# JDDZ.net
KiCad netlist of a schematic drawn in Altium Designer
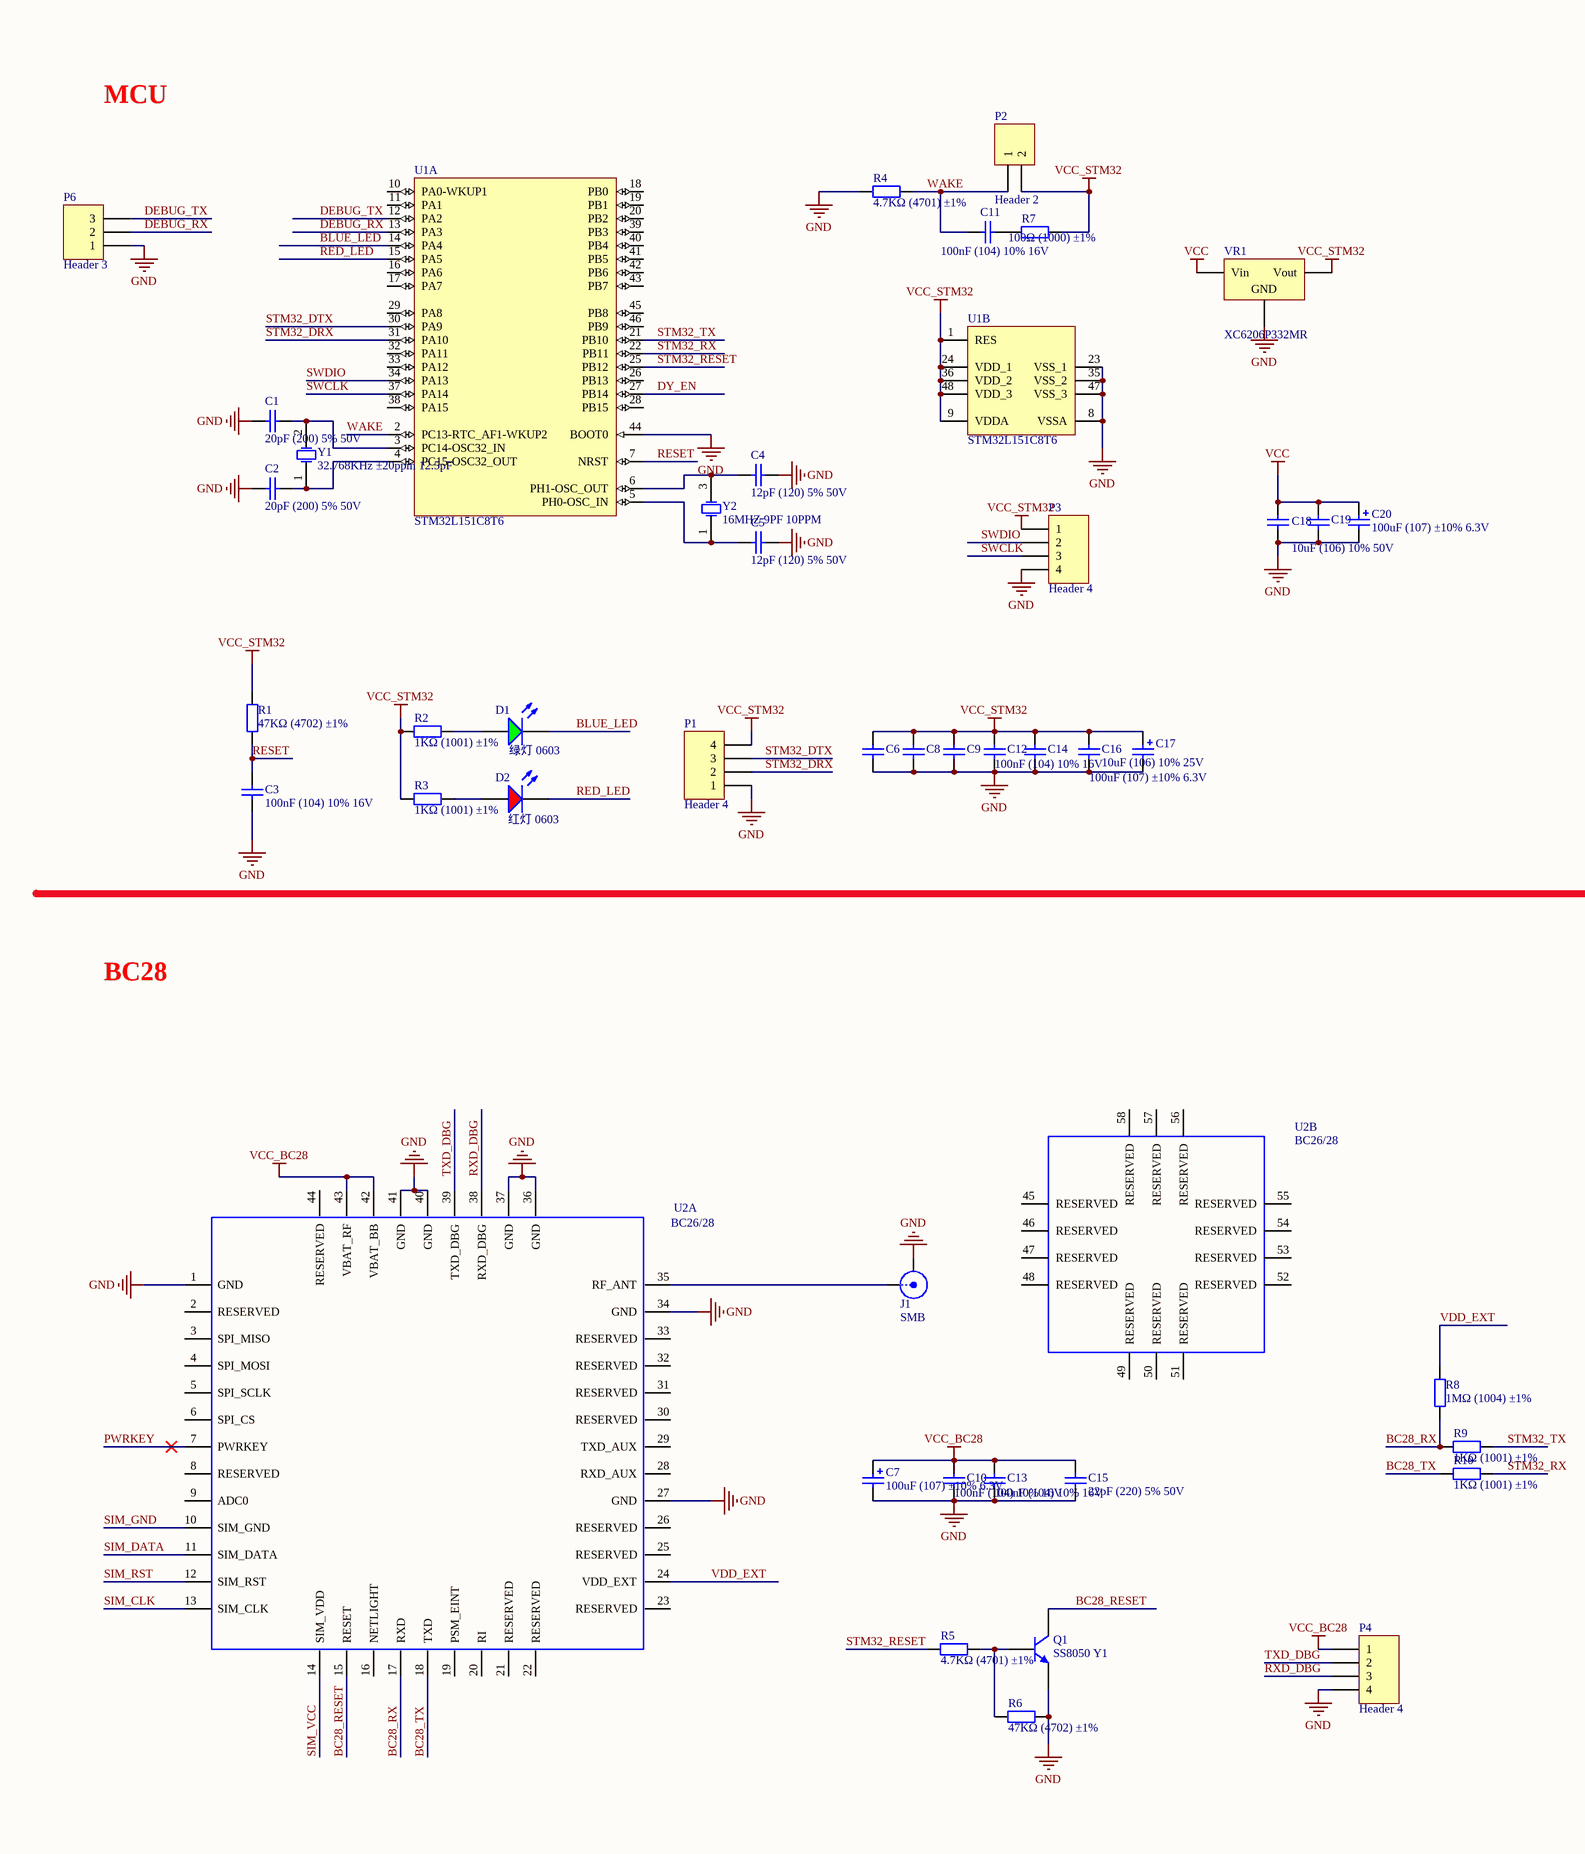
[diagram p0: JDDZ.SchDoc, left]
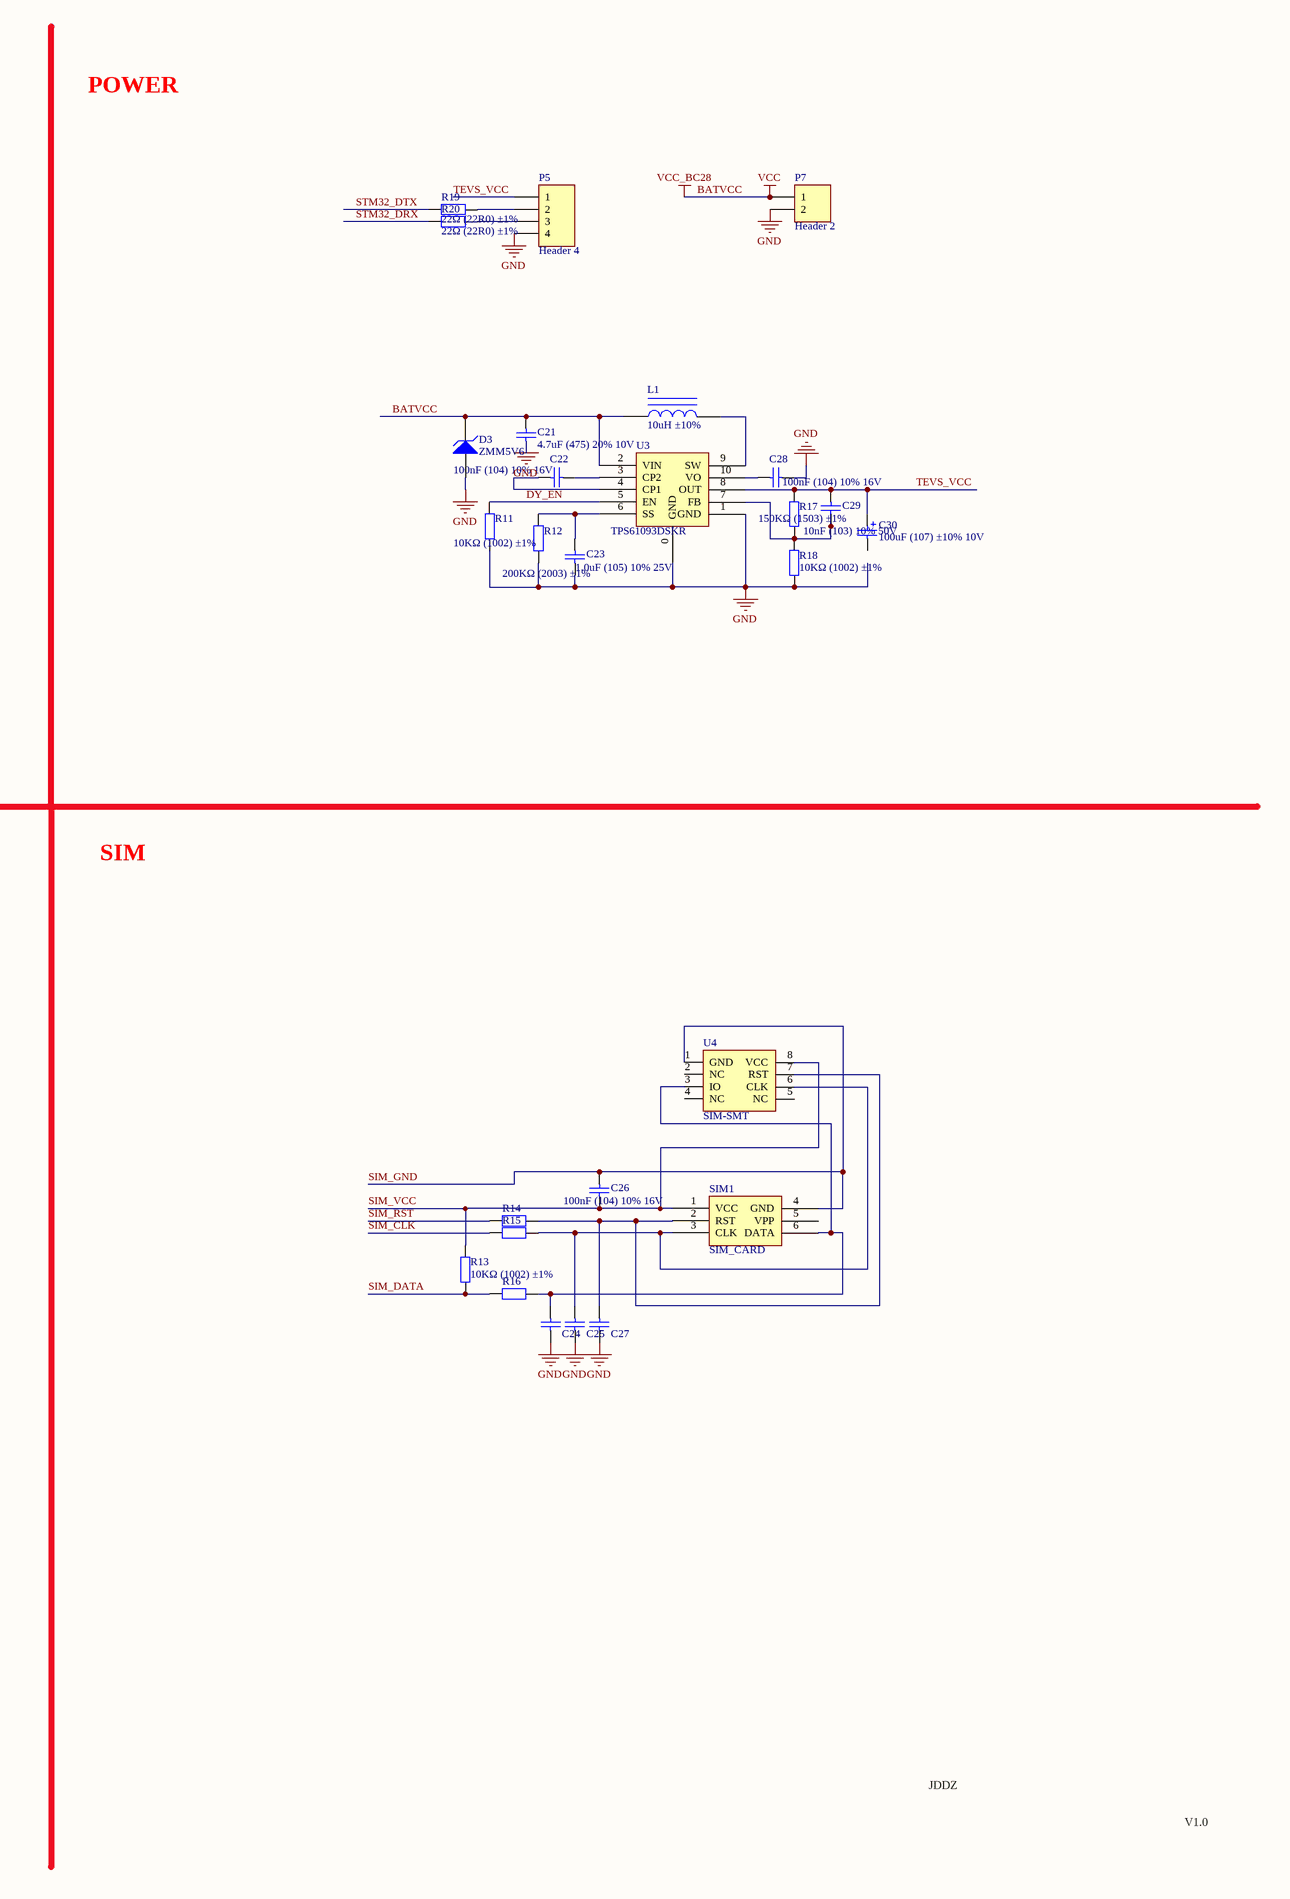
[diagram p1: JDDZ.SchDoc, right]

(export (version "E")
  (design (tool "Eeschema 10.0.6"))
  (components
    (comp (ref "C1")
      (value "20pF (200) 5% 50V")
      (footprint "0402_C")
      (description "贴片电容")
      (libsource (lib "Cap") (part "0402 20pF (200) 5% 50V"))
    )
    (comp (ref "C2")
      (value "20pF (200) 5% 50V")
      (footprint "0402_C")
      (description "贴片电容")
      (libsource (lib "Cap") (part "0402 20pF (200) 5% 50V"))
    )
    (comp (ref "C3")
      (value "100nF (104) 10% 16V")
      (footprint "0402_C")
      (description "贴片电容")
      (libsource (lib "Cap") (part "0402 100nF (104) 10% 16V"))
    )
    (comp (ref "C4")
      (value "12pF (120) 5% 50V")
      (footprint "0402_C")
      (description "贴片电容")
      (libsource (lib "Cap") (part "0402 12pF (120) 5% 50V"))
    )
    (comp (ref "C5")
      (value "12pF (120) 5% 50V")
      (footprint "0402_C")
      (description "贴片电容")
      (libsource (lib "Cap") (part "0402 12pF (120) 5% 50V"))
    )
    (comp (ref "C6")
      (value "100nF (104) 10% 16V")
      (footprint "0402_C")
      (description "贴片电容")
      (libsource (lib "Cap") (part "0402 100nF (104) 10% 16V"))
    )
    (comp (ref "C7")
      (value "100uF (107) ±10% 6.3V")
      (footprint "CASE-B_3528")
      (description "钽电容")
      (libsource (lib "Cap") (part "3528 100uF (107) 10% 6.3V"))
    )
    (comp (ref "C8")
      (value "100nF (104) 10% 16V")
      (footprint "0402_C")
      (description "贴片电容")
      (libsource (lib "Cap") (part "0402 100nF (104) 10% 16V"))
    )
    (comp (ref "C9")
      (value "100nF (104) 10% 16V")
      (footprint "0402_C")
      (description "贴片电容")
      (libsource (lib "Cap") (part "0402 100nF (104) 10% 16V"))
    )
    (comp (ref "C10")
      (value "100nF (104) 10% 16V")
      (footprint "0402_C")
      (description "贴片电容")
      (libsource (lib "Cap") (part "0402 100nF (104) 10% 16V"))
    )
    (comp (ref "C11")
      (value "100nF (104) 10% 16V")
      (footprint "0402_C")
      (description "贴片电容")
      (libsource (lib "Cap") (part "0402 100nF (104) 10% 16V"))
    )
    (comp (ref "C12")
      (value "100nF (104) 10% 16V")
      (footprint "0402_C")
      (description "贴片电容")
      (libsource (lib "Cap") (part "0402 100nF (104) 10% 16V"))
    )
    (comp (ref "C13")
      (value "100nF (104) 10% 16V")
      (footprint "0402_C")
      (description "贴片电容")
      (libsource (lib "Cap") (part "0402 100nF (104) 10% 16V"))
    )
    (comp (ref "C14")
      (value "100nF (104) 10% 16V")
      (footprint "0402_C")
      (description "贴片电容")
      (libsource (lib "Cap") (part "0402 100nF (104) 10% 16V"))
    )
    (comp (ref "C15")
      (value "22pF (220) 5% 50V")
      (footprint "0402_C")
      (description "贴片电容")
      (libsource (lib "Cap") (part "0402 22pF (220) 5% 50V"))
    )
    (comp (ref "C16")
      (value "10uF (106) 10% 25V")
      (footprint "0805_C")
      (description "贴片电容")
      (libsource (lib "Cap") (part "0805 10uF (106) 10% 25V"))
    )
    (comp (ref "C17")
      (value "100uF (107) ±10% 6.3V")
      (footprint "CASE-B_3528")
      (description "钽电容")
      (libsource (lib "Cap") (part "3528 100uF (107) 10% 6.3V"))
    )
    (comp (ref "C18")
      (value "10uF (106) 10% 10V")
      (footprint "0603_C")
      (description "贴片电容")
      (libsource (lib "Miscellaneous Devices LC") (part "0603 10uF (106) 10% 10V"))
    )
    (comp (ref "C19")
      (value "10uF (106) 10% 50V")
      (footprint "1206_C")
      (description "贴片电容")
      (libsource (lib "Miscellaneous Devices LC") (part "1206 10uF (106) 10% 50V"))
    )
    (comp (ref "C20")
      (value "100uF (107) ±10% 6.3V")
      (footprint "CASE-B_3528")
      (description "钽电容")
      (libsource (lib "Cap") (part "3528 100uF (107) 10% 6.3V"))
    )
    (comp (ref "C21")
      (value "4.7uF (475) 20% 10V")
      (footprint "0402_C")
      (description "贴片电容")
      (libsource (lib "Miscellaneous Devices LC") (part "0402 4.7uF (475) 20% 10V"))
    )
    (comp (ref "C22")
      (value "100nF (104) 10% 16V")
      (footprint "0402_C")
      (description "贴片电容")
      (libsource (lib "Miscellaneous Devices LC") (part "0402 100nF (104) 10% 16V"))
    )
    (comp (ref "C23")
      (value "1.0uF (105) 10% 25V")
      (footprint "0402_C")
      (description "贴片电容")
      (libsource (lib "Miscellaneous Devices LC") (part "0402 1.0uF (105) 10% 25V"))
    )
    (comp (ref "C24")
      (value "33pF (330) 5% 50V")
      (footprint "0402_C")
      (description "贴片电容")
      (libsource (lib "Cap") (part "0402 33pF (330) 5% 50V"))
    )
    (comp (ref "C25")
      (value "33pF (330) 5% 50V")
      (footprint "0402_C")
      (description "贴片电容")
      (libsource (lib "Cap") (part "0402 33pF (330) 5% 50V"))
    )
    (comp (ref "C26")
      (value "100nF (104) 10% 16V")
      (footprint "0402_C")
      (description "贴片电容")
      (libsource (lib "Cap") (part "0402 100nF (104) 10% 16V"))
    )
    (comp (ref "C27")
      (value "33pF (330) 5% 50V")
      (footprint "0402_C")
      (description "贴片电容")
      (libsource (lib "Cap") (part "0402 33pF (330) 5% 50V"))
    )
    (comp (ref "C28")
      (value "100nF (104) 10% 16V")
      (footprint "0402_C")
      (description "贴片电容")
      (libsource (lib "Miscellaneous Devices LC") (part "0402 100nF (104) 10% 16V"))
    )
    (comp (ref "C29")
      (value "10nF (103) 10% 50V")
      (footprint "0402_C")
      (description "贴片电容")
      (libsource (lib "Miscellaneous Devices LC") (part "0402 10nF (103) 10% 50V"))
    )
    (comp (ref "C30")
      (value "100uF (107) ±10% 10V")
      (footprint "CASE-B_3528")
      (description "钽电容")
      (libsource (lib "Miscellaneous Devices LC") (part "3528 100uF (107) 10% 6.3V"))
    )
    (comp (ref "D1")
      (value "绿灯 0603")
      (footprint "0603_LED_S1")
      (description "发光二极管")
      (libsource (lib "LED") (part "0603 绿灯"))
    )
    (comp (ref "D2")
      (value "红灯 0603")
      (footprint "0603_LED_S1")
      (description "发光二极管")
      (libsource (lib "LED") (part "0603 红灯"))
    )
    (comp (ref "D3")
      (value "ZMM5V6")
      (footprint "LL-34")
      (description "稳压二极管")
      (libsource (lib "Zener") (part "LL-34 ZMM5V6"))
    )
    (comp (ref "J1")
      (value "SMB")
      (footprint "IPX_SMT")
      (description "SMB Straight Connector")
      (fields (field (name "PUBLISHER") "Altium Limited"))
      (libsource (lib "BC28开发板SCH封装") (part "SMB"))
    )
    (comp (ref "L1")
      (value "10uH ±10%")
      (footprint "0603_L")
      (description "贴片电感")
      (libsource (lib "Miscellaneous Devices LC") (part "0603 10uH 10%"))
    )
    (comp (ref "P1")
      (value "Header 4")
      (footprint "HDR1X4")
      (description "Header, 4-Pin")
      (fields (field (name "PUBLISHER") "Altium Limited"))
      (libsource (lib "") (part "Header 4_1"))
    )
    (comp (ref "P2")
      (value "Header 2")
      (footprint "HDR1X2")
      (description "Header, 2-Pin")
      (fields (field (name "PUBLISHER") "Altium Limited"))
      (libsource (lib "Miscellaneous Connectors") (part "Header 2"))
    )
    (comp (ref "P3")
      (value "Header 4")
      (footprint "HDR1X4")
      (description "Header, 4-Pin")
      (fields (field (name "PUBLISHER") "Altium Limited"))
      (libsource (lib "Miscellaneous Connectors") (part "Header 4"))
    )
    (comp (ref "P4")
      (value "Header 4")
      (footprint "HDR1X4")
      (description "Header, 4-Pin")
      (fields (field (name "PUBLISHER") "Altium Limited"))
      (libsource (lib "Miscellaneous Connectors") (part "Header 4"))
    )
    (comp (ref "P5")
      (value "Header 4")
      (footprint "HDR1X4")
      (description "Header, 4-Pin")
      (fields (field (name "PUBLISHER") "Altium Limited"))
      (libsource (lib "Miscellaneous Connectors") (part "Header 4"))
    )
    (comp (ref "P6")
      (value "Header 3")
      (footprint "HDR1X3")
      (description "Header, 3-Pin")
      (fields (field (name "PUBLISHER") "Altium Limited"))
      (libsource (lib "Miscellaneous Connectors") (part "Header 3"))
    )
    (comp (ref "P7")
      (value "Header 2")
      (footprint "HDR1X2")
      (description "Header, 2-Pin")
      (fields (field (name "PUBLISHER") "Altium Limited"))
      (libsource (lib "") (part "Header 2_1"))
    )
    (comp (ref "Q1")
      (value "SS8050 Y1")
      (footprint "SOT-23(SOT-23-3)")
      (description "三极管")
      (libsource (lib "Transistor_NPN") (part "SOT-23 SS8050 Y1"))
    )
    (comp (ref "R1")
      (value "47KΩ (4702) ±1%")
      (footprint "0402_R")
      (description "贴片电阻")
      (libsource (lib "RES") (part "0402 47KΩ (4702) 1%"))
    )
    (comp (ref "R2")
      (value "1KΩ (1001) ±1%")
      (footprint "0402_R")
      (description "贴片电阻")
      (libsource (lib "RES") (part "0402 1KΩ (1001) 1%"))
    )
    (comp (ref "R3")
      (value "1KΩ (1001) ±1%")
      (footprint "0402_R")
      (description "贴片电阻")
      (libsource (lib "RES") (part "0402 1KΩ (1001) 1%"))
    )
    (comp (ref "R4")
      (value "4.7KΩ (4701) ±1%")
      (footprint "0402_R")
      (description "贴片电阻")
      (libsource (lib "RES") (part "0402 4.7KΩ (4701) 1%"))
    )
    (comp (ref "R5")
      (value "4.7KΩ (4701) ±1%")
      (footprint "0402_R")
      (description "贴片电阻")
      (libsource (lib "RES") (part "0402 4.7KΩ (4701) 1%"))
    )
    (comp (ref "R6")
      (value "47KΩ (4702) ±1%")
      (footprint "0402_R")
      (description "贴片电阻")
      (libsource (lib "") (part "0402 47KΩ (4702) 1%_1"))
    )
    (comp (ref "R7")
      (value "100Ω (1000) ±1%")
      (footprint "0402_R")
      (description "贴片电阻")
      (libsource (lib "RES") (part "0402 100Ω (1000) 1%"))
    )
    (comp (ref "R8")
      (value "1MΩ (1004) ±1%")
      (footprint "0402_R")
      (description "贴片电阻")
      (libsource (lib "RES") (part "0402 1MΩ (1004) 1%"))
    )
    (comp (ref "R9")
      (value "1KΩ (1001) ±1%")
      (footprint "0402_R")
      (description "贴片电阻")
      (libsource (lib "RES") (part "0402 1KΩ (1001) 1%"))
    )
    (comp (ref "R10")
      (value "1KΩ (1001) ±1%")
      (footprint "0402_R")
      (description "贴片电阻")
      (libsource (lib "RES") (part "0402 1KΩ (1001) 1%"))
    )
    (comp (ref "R11")
      (value "10KΩ (1002) ±1%")
      (footprint "0402_R")
      (description "贴片电阻")
      (libsource (lib "Miscellaneous Devices LC") (part "0402 10KΩ (1002) 1%"))
    )
    (comp (ref "R12")
      (value "200KΩ (2003) ±1%")
      (footprint "0402_R")
      (description "贴片电阻")
      (libsource (lib "Miscellaneous Devices LC") (part "0402 200KΩ (2003) 1%"))
    )
    (comp (ref "R13")
      (value "10KΩ (1002) ±1%")
      (footprint "0402_R")
      (description "贴片电阻")
      (libsource (lib "RES") (part "0402 10KΩ (1002) 1%"))
    )
    (comp (ref "R14")
      (value "22Ω (22R0) ±1%")
      (footprint "0402_R")
      (description "贴片电阻")
      (libsource (lib "RES") (part "0402 22Ω (22R0) 1%"))
    )
    (comp (ref "R15")
      (value "22Ω (22R0) ±1%")
      (footprint "0402_R")
      (description "贴片电阻")
      (libsource (lib "RES") (part "0402 22Ω (22R0) 1%"))
    )
    (comp (ref "R16")
      (value "22Ω (22R0) ±1%")
      (footprint "0402_R")
      (description "贴片电阻")
      (libsource (lib "RES") (part "0402 22Ω (22R0) 1%"))
    )
    (comp (ref "R17")
      (value "150KΩ (1503) ±1%")
      (footprint "0402_R")
      (description "贴片电阻")
      (libsource (lib "RES") (part "0402 150KΩ (1503) 1%"))
    )
    (comp (ref "R18")
      (value "10KΩ (1002) ±1%")
      (footprint "0402_R")
      (description "贴片电阻")
      (libsource (lib "Miscellaneous Devices LC") (part "0402 10KΩ (1002) 1%"))
    )
    (comp (ref "R19")
      (value "22Ω (22R0) ±1%")
      (footprint "0402_R")
      (description "贴片电阻")
      (libsource (lib "RES") (part "0402 22Ω (22R0) 1%"))
    )
    (comp (ref "R20")
      (value "22Ω (22R0) ±1%")
      (footprint "0402_R")
      (description "贴片电阻")
      (libsource (lib "RES") (part "0402 22Ω (22R0) 1%"))
    )
    (comp (ref "SIM1")
      (value "SIM_CARD")
      (footprint "microSIMauto")
      (libsource (lib "BC28开发板SCH封装") (part "SIM_CARD"))
    )
    (comp (ref "U1")
      (value "STM32L151C8T6")
      (footprint "LQFP-48_7x7x05P")
      (description "ARM")
      (libsource (lib "MCU") (part "STM32L151C8T6"))
    )
    (comp (ref "U2") (value "BC26/28") (footprint "bc26") (libsource (lib "BC28开发板SCH封装") (part "BC26")))
    (comp (ref "U3")
      (value "TPS61093DSKR")
      (footprint "LC-WSON-10_2.5x2.5mm")
      (libsource (lib "TEV_Collection") (part "TPS61093DSKR"))
    )
    (comp (ref "U4") (value "SIM-SMT") (footprint "SIM-SOP") (libsource (lib "M5310") (part "SIM-SMT")))
    (comp (ref "VR1")
      (value "XC6206P332MR")
      (footprint "SOT-23-3L")
      (description "低压差线性稳压(LDO)")
      (libsource (lib "LDO") (part "SOT-23 XC6206P332MR"))
    )
    (comp (ref "Y1")
      (value "32.768KHz ±20ppm 12.5pF")
      (footprint "SMD-3215_2P FC - 135")
      (description "贴片晶振")
      (libsource (lib "CrystalOscillator") (part "SMD-3215_2P 32.768KHz 20ppm 12.5pF"))
    )
    (comp (ref "Y2")
      (value "16MHZ 9PF 10PPM")
      (footprint "SMD-3225_4P")
      (description "贴片晶振")
      (libsource (lib "CrystalOscillator") (part "SMD-3225_4P  16MHZ 9PF 10PPM"))
    )
  )
  (nets
    (net (code "1") (name "/BC28_RESET") (class "Default")
      (node (ref "Q1") (pin "3") (pinfunction "C_3") (pintype "passive"))
      (node (ref "U2") (pin "15") (pinfunction "RESET_15") (pintype "passive"))
    )
    (net (code "2") (name "/BC28_RX") (class "Default")
      (node (ref "R8") (pin "1") (pinfunction "1_1") (pintype "passive"))
      (node (ref "R9") (pin "1") (pinfunction "1_1") (pintype "passive"))
      (node (ref "U2") (pin "17") (pinfunction "RXD_17") (pintype "passive"))
    )
    (net (code "3") (name "/BC28_TX") (class "Default")
      (node (ref "R10") (pin "1") (pinfunction "1_1") (pintype "passive"))
      (node (ref "U2") (pin "18") (pinfunction "TXD_18") (pintype "passive"))
    )
    (net (code "4") (name "/BLUE_LED") (class "Default")
      (node (ref "D1") (pin "K") (pinfunction "K_K") (pintype "passive"))
      (node (ref "U1") (pin "14") (pinfunction "PA4_14") (pintype "bidirectional"))
    )
    (net (code "5") (name "/DEBUG_RX") (class "Default")
      (node (ref "P6") (pin "2") (pinfunction "2_2") (pintype "passive"))
      (node (ref "U1") (pin "13") (pinfunction "PA3_13") (pintype "bidirectional"))
    )
    (net (code "6") (name "/DEBUG_TX") (class "Default")
      (node (ref "P6") (pin "3") (pinfunction "3_3") (pintype "passive"))
      (node (ref "U1") (pin "12") (pinfunction "PA2_12") (pintype "bidirectional"))
    )
    (net (code "7") (name "/DY_EN") (class "Default")
      (node (ref "R11") (pin "2") (pinfunction "2_2") (pintype "passive"))
      (node (ref "U1") (pin "27") (pinfunction "PB14_27") (pintype "bidirectional"))
      (node (ref "U3") (pin "5") (pinfunction "EN_5") (pintype "passive"))
    )
    (net (code "8") (name "/PWRKEY") (class "Default")
      (node (ref "U2") (pin "7") (pinfunction "PWRKEY_7") (pintype "passive"))
    )
    (net (code "9") (name "/RED_LED") (class "Default")
      (node (ref "D2") (pin "K") (pinfunction "K_K") (pintype "passive"))
      (node (ref "U1") (pin "15") (pinfunction "PA5_15") (pintype "bidirectional"))
    )
    (net (code "10") (name "/RESET") (class "Default")
      (node (ref "C3") (pin "2") (pinfunction "2_2") (pintype "passive"))
      (node (ref "R1") (pin "1") (pinfunction "1_1") (pintype "passive"))
      (node (ref "U1") (pin "7") (pinfunction "NRST_7") (pintype "bidirectional"))
    )
    (net (code "11") (name "/RXD_DBG") (class "Default")
      (node (ref "P4") (pin "3") (pinfunction "3_3") (pintype "passive"))
      (node (ref "U2") (pin "38") (pinfunction "RXD_DBG_38") (pintype "passive"))
    )
    (net (code "12") (name "/SIM_CLK") (class "Default")
      (node (ref "R15") (pin "1") (pinfunction "1_1") (pintype "passive"))
      (node (ref "U2") (pin "13") (pinfunction "SIM_CLK_13") (pintype "passive"))
    )
    (net (code "13") (name "/SIM_DATA") (class "Default")
      (node (ref "R13") (pin "1") (pinfunction "1_1") (pintype "passive"))
      (node (ref "R16") (pin "1") (pinfunction "1_1") (pintype "passive"))
      (node (ref "U2") (pin "11") (pinfunction "SIM_DATA_11") (pintype "passive"))
    )
    (net (code "14") (name "/SIM_GND") (class "Default")
      (node (ref "C26") (pin "2") (pinfunction "2_2") (pintype "passive"))
      (node (ref "SIM1") (pin "4") (pinfunction "GND_4") (pintype "passive"))
      (node (ref "U2") (pin "10") (pinfunction "SIM_GND_10") (pintype "passive"))
      (node (ref "U4") (pin "1") (pinfunction "GND_1") (pintype "passive"))
    )
    (net (code "15") (name "/SIM_RST") (class "Default")
      (node (ref "R14") (pin "1") (pinfunction "1_1") (pintype "passive"))
      (node (ref "U2") (pin "12") (pinfunction "SIM_RST_12") (pintype "passive"))
    )
    (net (code "16") (name "/SIM_VCC") (class "Default")
      (node (ref "C26") (pin "1") (pinfunction "1_1") (pintype "passive"))
      (node (ref "R13") (pin "2") (pinfunction "2_2") (pintype "passive"))
      (node (ref "SIM1") (pin "1") (pinfunction "VCC_1") (pintype "passive"))
      (node (ref "U2") (pin "14") (pinfunction "SIM_VDD_14") (pintype "passive"))
      (node (ref "U4") (pin "8") (pinfunction "VCC_8") (pintype "passive"))
    )
    (net (code "17") (name "/STM32_DRX") (class "Default")
      (node (ref "P1") (pin "2") (pinfunction "2_2") (pintype "passive"))
      (node (ref "R20") (pin "1") (pinfunction "1_1") (pintype "passive"))
      (node (ref "U1") (pin "31") (pinfunction "PA10_31") (pintype "bidirectional"))
    )
    (net (code "18") (name "/STM32_DTX") (class "Default")
      (node (ref "P1") (pin "3") (pinfunction "3_3") (pintype "passive"))
      (node (ref "R19") (pin "1") (pinfunction "1_1") (pintype "passive"))
      (node (ref "U1") (pin "30") (pinfunction "PA9_30") (pintype "bidirectional"))
    )
    (net (code "19") (name "/STM32_RESET") (class "Default")
      (node (ref "R5") (pin "1") (pinfunction "1_1") (pintype "passive"))
      (node (ref "U1") (pin "25") (pinfunction "PB12_25") (pintype "bidirectional"))
    )
    (net (code "20") (name "/STM32_RX") (class "Default")
      (node (ref "R10") (pin "2") (pinfunction "2_2") (pintype "passive"))
      (node (ref "U1") (pin "22") (pinfunction "PB11_22") (pintype "bidirectional"))
    )
    (net (code "21") (name "/STM32_TX") (class "Default")
      (node (ref "R9") (pin "2") (pinfunction "2_2") (pintype "passive"))
      (node (ref "U1") (pin "21") (pinfunction "PB10_21") (pintype "bidirectional"))
    )
    (net (code "22") (name "/SWCLK") (class "Default")
      (node (ref "P3") (pin "3") (pinfunction "3_3") (pintype "passive"))
      (node (ref "U1") (pin "37") (pinfunction "PA14_37") (pintype "bidirectional"))
    )
    (net (code "23") (name "/SWDIO") (class "Default")
      (node (ref "P3") (pin "2") (pinfunction "2_2") (pintype "passive"))
      (node (ref "U1") (pin "34") (pinfunction "PA13_34") (pintype "bidirectional"))
    )
    (net (code "24") (name "/TEVS_VCC") (class "Default")
      (node (ref "C29") (pin "2") (pinfunction "2_2") (pintype "passive"))
      (node (ref "C30") (pin "1") (pinfunction "1_1") (pintype "passive"))
      (node (ref "P5") (pin "1") (pinfunction "1_1") (pintype "passive"))
      (node (ref "R17") (pin "2") (pinfunction "2_2") (pintype "passive"))
      (node (ref "U3") (pin "8") (pinfunction "OUT_8") (pintype "passive"))
    )
    (net (code "25") (name "/TXD_DBG") (class "Default")
      (node (ref "P4") (pin "2") (pinfunction "2_2") (pintype "passive"))
      (node (ref "U2") (pin "39") (pinfunction "TXD_DBG_39") (pintype "passive"))
    )
    (net (code "26") (name "/VDD_EXT") (class "Default")
      (node (ref "R8") (pin "2") (pinfunction "2_2") (pintype "passive"))
      (node (ref "U2") (pin "24") (pinfunction "VDD_EXT_24") (pintype "passive"))
    )
    (net (code "27") (name "/WAKE") (class "Default")
      (node (ref "C11") (pin "1") (pinfunction "1_1") (pintype "passive"))
      (node (ref "P2") (pin "1") (pinfunction "1_1") (pintype "passive"))
      (node (ref "R4") (pin "2") (pinfunction "2_2") (pintype "passive"))
      (node (ref "U1") (pin "2") (pinfunction "PC13-RTC_AF1-WKUP2_2") (pintype "bidirectional"))
    )
    (net (code "28") (name "GND") (class "Default")
      (node (ref "C1") (pin "1") (pinfunction "1_1") (pintype "passive"))
      (node (ref "C10") (pin "1") (pinfunction "1_1") (pintype "passive"))
      (node (ref "C12") (pin "1") (pinfunction "1_1") (pintype "passive"))
      (node (ref "C13") (pin "1") (pinfunction "1_1") (pintype "passive"))
      (node (ref "C14") (pin "1") (pinfunction "1_1") (pintype "passive"))
      (node (ref "C15") (pin "1") (pinfunction "1_1") (pintype "passive"))
      (node (ref "C16") (pin "1") (pinfunction "1_1") (pintype "passive"))
      (node (ref "C17") (pin "2") (pinfunction "2_2") (pintype "passive"))
      (node (ref "C18") (pin "1") (pinfunction "1_1") (pintype "passive"))
      (node (ref "C19") (pin "1") (pinfunction "1_1") (pintype "passive"))
      (node (ref "C2") (pin "1") (pinfunction "1_1") (pintype "passive"))
      (node (ref "C20") (pin "2") (pinfunction "2_2") (pintype "passive"))
      (node (ref "C21") (pin "1") (pinfunction "1_1") (pintype "passive"))
      (node (ref "C23") (pin "1") (pinfunction "1_1") (pintype "passive"))
      (node (ref "C24") (pin "1") (pinfunction "1_1") (pintype "passive"))
      (node (ref "C25") (pin "1") (pinfunction "1_1") (pintype "passive"))
      (node (ref "C27") (pin "1") (pinfunction "1_1") (pintype "passive"))
      (node (ref "C28") (pin "2") (pinfunction "2_2") (pintype "passive"))
      (node (ref "C3") (pin "1") (pinfunction "1_1") (pintype "passive"))
      (node (ref "C4") (pin "2") (pinfunction "2_2") (pintype "passive"))
      (node (ref "C5") (pin "2") (pinfunction "2_2") (pintype "passive"))
      (node (ref "C6") (pin "1") (pinfunction "1_1") (pintype "passive"))
      (node (ref "C7") (pin "2") (pinfunction "2_2") (pintype "passive"))
      (node (ref "C8") (pin "1") (pinfunction "1_1") (pintype "passive"))
      (node (ref "C9") (pin "1") (pinfunction "1_1") (pintype "passive"))
      (node (ref "D3") (pin "1") (pinfunction "A_1") (pintype "passive"))
      (node (ref "J1") (pin "2") (pinfunction "Y_2") (pintype "passive"))
      (node (ref "P1") (pin "1") (pinfunction "1_1") (pintype "passive"))
      (node (ref "P3") (pin "4") (pinfunction "4_4") (pintype "passive"))
      (node (ref "P4") (pin "4") (pinfunction "4_4") (pintype "passive"))
      (node (ref "P5") (pin "4") (pinfunction "4_4") (pintype "passive"))
      (node (ref "P6") (pin "1") (pinfunction "1_1") (pintype "passive"))
      (node (ref "P7") (pin "2") (pinfunction "2_2") (pintype "passive"))
      (node (ref "Q1") (pin "2") (pinfunction "E_2") (pintype "passive"))
      (node (ref "R11") (pin "1") (pinfunction "1_1") (pintype "passive"))
      (node (ref "R12") (pin "1") (pinfunction "1_1") (pintype "passive"))
      (node (ref "R18") (pin "1") (pinfunction "1_1") (pintype "passive"))
      (node (ref "R4") (pin "1") (pinfunction "1_1") (pintype "passive"))
      (node (ref "R6") (pin "2") (pinfunction "2_2") (pintype "passive"))
      (node (ref "U1") (pin "23") (pinfunction "VSS_1_23") (pintype "power_in"))
      (node (ref "U1") (pin "35") (pinfunction "VSS_2_35") (pintype "power_in"))
      (node (ref "U1") (pin "44") (pinfunction "BOOT0_44") (pintype "input"))
      (node (ref "U1") (pin "47") (pinfunction "VSS_3_47") (pintype "power_in"))
      (node (ref "U1") (pin "8") (pinfunction "VSSA_8") (pintype "power_in"))
      (node (ref "U2") (pin "1") (pinfunction "GND_1") (pintype "passive"))
      (node (ref "U2") (pin "27") (pinfunction "GND_27") (pintype "passive"))
      (node (ref "U2") (pin "34") (pinfunction "GND_34") (pintype "passive"))
      (node (ref "U2") (pin "36") (pinfunction "GND_36") (pintype "passive"))
      (node (ref "U2") (pin "37") (pinfunction "GND_37") (pintype "passive"))
      (node (ref "U2") (pin "40") (pinfunction "GND_40") (pintype "passive"))
      (node (ref "U2") (pin "41") (pinfunction "GND_41") (pintype "passive"))
      (node (ref "U3") (pin "0") (pinfunction "GND_0") (pintype "power_in"))
      (node (ref "U3") (pin "1") (pinfunction "GND_1") (pintype "power_in"))
      (node (ref "VR1") (pin "1") (pinfunction "GND_1") (pintype "passive"))
    )
    (net (code "29") (name "Net-(C11-Pad2)") (class "Default")
      (node (ref "C11") (pin "2") (pinfunction "2_2") (pintype "passive"))
      (node (ref "R7") (pin "1") (pinfunction "1_1") (pintype "passive"))
    )
    (net (code "30") (name "Net-(D1-PadA)") (class "Default")
      (node (ref "D1") (pin "A") (pinfunction "A_A") (pintype "passive"))
      (node (ref "R2") (pin "2") (pinfunction "2_2") (pintype "passive"))
    )
    (net (code "31") (name "Net-(D2-PadA)") (class "Default")
      (node (ref "D2") (pin "A") (pinfunction "A_A") (pintype "passive"))
      (node (ref "R3") (pin "2") (pinfunction "2_2") (pintype "passive"))
    )
    (net (code "32") (name "Net-(J1-X)") (class "Default")
      (node (ref "J1") (pin "1") (pinfunction "X_1") (pintype "passive"))
      (node (ref "U2") (pin "35") (pinfunction "RF_ANT_35") (pintype "passive"))
    )
    (net (code "33") (name "Net-(P5-Pad2)") (class "Default")
      (node (ref "P5") (pin "2") (pinfunction "2_2") (pintype "passive"))
      (node (ref "R19") (pin "2") (pinfunction "2_2") (pintype "passive"))
    )
    (net (code "34") (name "Net-(P5-Pad3)") (class "Default")
      (node (ref "P5") (pin "3") (pinfunction "3_3") (pintype "passive"))
      (node (ref "R20") (pin "2") (pinfunction "2_2") (pintype "passive"))
    )
    (net (code "35") (name "Net-(Q1-B)") (class "Default")
      (node (ref "Q1") (pin "1") (pinfunction "B_1") (pintype "passive"))
      (node (ref "R5") (pin "2") (pinfunction "2_2") (pintype "passive"))
      (node (ref "R6") (pin "1") (pinfunction "1_1") (pintype "passive"))
    )
    (net (code "36") (name "Net-(SIM1-CLK)") (class "Default")
      (node (ref "C25") (pin "2") (pinfunction "2_2") (pintype "passive"))
      (node (ref "R15") (pin "2") (pinfunction "2_2") (pintype "passive"))
      (node (ref "SIM1") (pin "3") (pinfunction "CLK_3") (pintype "passive"))
      (node (ref "U4") (pin "6") (pinfunction "CLK_6") (pintype "passive"))
    )
    (net (code "37") (name "Net-(SIM1-DATA)") (class "Default")
      (node (ref "C24") (pin "2") (pinfunction "2_2") (pintype "passive"))
      (node (ref "R16") (pin "2") (pinfunction "2_2") (pintype "passive"))
      (node (ref "SIM1") (pin "6") (pinfunction "DATA_6") (pintype "passive"))
      (node (ref "U4") (pin "3") (pinfunction "IO_3") (pintype "passive"))
    )
    (net (code "38") (name "Net-(SIM1-RST)") (class "Default")
      (node (ref "C27") (pin "2") (pinfunction "2_2") (pintype "passive"))
      (node (ref "R14") (pin "2") (pinfunction "2_2") (pintype "passive"))
      (node (ref "SIM1") (pin "2") (pinfunction "RST_2") (pintype "passive"))
      (node (ref "U4") (pin "7") (pinfunction "RST_7") (pintype "passive"))
    )
    (net (code "39") (name "Net-(U1A-PC14-OSC32_IN)") (class "Default")
      (node (ref "C1") (pin "2") (pinfunction "2_2") (pintype "passive"))
      (node (ref "U1") (pin "3") (pinfunction "PC14-OSC32_IN_3") (pintype "bidirectional"))
      (node (ref "Y1") (pin "2") (pinfunction "OSC2_2") (pintype "passive"))
    )
    (net (code "40") (name "Net-(U1A-PC15-OSC32_OUT)") (class "Default")
      (node (ref "C2") (pin "2") (pinfunction "2_2") (pintype "passive"))
      (node (ref "U1") (pin "4") (pinfunction "PC15-OSC32_OUT_4") (pintype "bidirectional"))
      (node (ref "Y1") (pin "1") (pinfunction "OSC1_1") (pintype "passive"))
    )
    (net (code "41") (name "Net-(U1A-PH0-OSC_IN)") (class "Default")
      (node (ref "C5") (pin "1") (pinfunction "1_1") (pintype "passive"))
      (node (ref "U1") (pin "5") (pinfunction "PH0-OSC_IN_5") (pintype "bidirectional"))
      (node (ref "Y2") (pin "1") (pinfunction "OSC1_1") (pintype "passive"))
    )
    (net (code "42") (name "Net-(U1A-PH1-OSC_OUT)") (class "Default")
      (node (ref "C4") (pin "1") (pinfunction "1_1") (pintype "passive"))
      (node (ref "U1") (pin "6") (pinfunction "PH1-OSC_OUT_6") (pintype "bidirectional"))
      (node (ref "Y2") (pin "3") (pinfunction "OSC2_3") (pintype "passive"))
    )
    (net (code "43") (name "Net-(U3-CP1)") (class "Default")
      (node (ref "C22") (pin "1") (pinfunction "1_1") (pintype "passive"))
      (node (ref "U3") (pin "4") (pinfunction "CP1_4") (pintype "passive"))
    )
    (net (code "44") (name "Net-(U3-CP2)") (class "Default")
      (node (ref "C22") (pin "2") (pinfunction "2_2") (pintype "passive"))
      (node (ref "U3") (pin "3") (pinfunction "CP2_3") (pintype "passive"))
    )
    (net (code "45") (name "Net-(U3-FB)") (class "Default")
      (node (ref "C29") (pin "1") (pinfunction "1_1") (pintype "passive"))
      (node (ref "R17") (pin "1") (pinfunction "1_1") (pintype "passive"))
      (node (ref "R18") (pin "2") (pinfunction "2_2") (pintype "passive"))
      (node (ref "U3") (pin "7") (pinfunction "FB_7") (pintype "passive"))
    )
    (net (code "46") (name "Net-(U3-SS)") (class "Default")
      (node (ref "C23") (pin "2") (pinfunction "2_2") (pintype "passive"))
      (node (ref "R12") (pin "2") (pinfunction "2_2") (pintype "passive"))
      (node (ref "U3") (pin "6") (pinfunction "SS_6") (pintype "passive"))
    )
    (net (code "47") (name "Net-(U3-SW)") (class "Default")
      (node (ref "L1") (pin "2") (pinfunction "2_2") (pintype "passive"))
      (node (ref "U3") (pin "9") (pinfunction "SW_9") (pintype "passive"))
    )
    (net (code "48") (name "Net-(U3-VO)") (class "Default")
      (node (ref "C28") (pin "1") (pinfunction "1_1") (pintype "passive"))
      (node (ref "U3") (pin "10") (pinfunction "VO_10") (pintype "passive"))
    )
    (net (code "49") (name "VCC") (class "Default")
      (node (ref "C10") (pin "2") (pinfunction "2_2") (pintype "passive"))
      (node (ref "C13") (pin "2") (pinfunction "2_2") (pintype "passive"))
      (node (ref "C15") (pin "2") (pinfunction "2_2") (pintype "passive"))
      (node (ref "C18") (pin "2") (pinfunction "2_2") (pintype "passive"))
      (node (ref "C19") (pin "2") (pinfunction "2_2") (pintype "passive"))
      (node (ref "C20") (pin "1") (pinfunction "1_1") (pintype "passive"))
      (node (ref "C21") (pin "2") (pinfunction "2_2") (pintype "passive"))
      (node (ref "C7") (pin "1") (pinfunction "1_1") (pintype "passive"))
      (node (ref "D3") (pin "2") (pinfunction "K_2") (pintype "passive"))
      (node (ref "L1") (pin "1") (pinfunction "1_1") (pintype "passive"))
      (node (ref "P4") (pin "1") (pinfunction "1_1") (pintype "passive"))
      (node (ref "P7") (pin "1") (pinfunction "1_1") (pintype "passive"))
      (node (ref "U2") (pin "42") (pinfunction "VBAT_BB_42") (pintype "passive"))
      (node (ref "U2") (pin "43") (pinfunction "VBAT_RF_43") (pintype "passive"))
      (node (ref "U3") (pin "2") (pinfunction "VIN_2") (pintype "passive"))
      (node (ref "VR1") (pin "3") (pinfunction "Vin_3") (pintype "passive"))
    )
    (net (code "50") (name "VCC_STM32") (class "Default")
      (node (ref "C12") (pin "2") (pinfunction "2_2") (pintype "passive"))
      (node (ref "C14") (pin "2") (pinfunction "2_2") (pintype "passive"))
      (node (ref "C16") (pin "2") (pinfunction "2_2") (pintype "passive"))
      (node (ref "C17") (pin "1") (pinfunction "1_1") (pintype "passive"))
      (node (ref "C6") (pin "2") (pinfunction "2_2") (pintype "passive"))
      (node (ref "C8") (pin "2") (pinfunction "2_2") (pintype "passive"))
      (node (ref "C9") (pin "2") (pinfunction "2_2") (pintype "passive"))
      (node (ref "P1") (pin "4") (pinfunction "4_4") (pintype "passive"))
      (node (ref "P2") (pin "2") (pinfunction "2_2") (pintype "passive"))
      (node (ref "P3") (pin "1") (pinfunction "1_1") (pintype "passive"))
      (node (ref "R1") (pin "2") (pinfunction "2_2") (pintype "passive"))
      (node (ref "R2") (pin "1") (pinfunction "1_1") (pintype "passive"))
      (node (ref "R3") (pin "1") (pinfunction "1_1") (pintype "passive"))
      (node (ref "R7") (pin "2") (pinfunction "2_2") (pintype "passive"))
      (node (ref "U1") (pin "1") (pinfunction "RES_1") (pintype "power_in"))
      (node (ref "U1") (pin "24") (pinfunction "VDD_1_24") (pintype "power_in"))
      (node (ref "U1") (pin "36") (pinfunction "VDD_2_36") (pintype "power_in"))
      (node (ref "U1") (pin "48") (pinfunction "VDD_3_48") (pintype "power_in"))
      (node (ref "U1") (pin "9") (pinfunction "VDDA_9") (pintype "power_in"))
      (node (ref "VR1") (pin "2") (pinfunction "Vout_2") (pintype "passive"))
    )
    (net (code "51") (name "unconnected-(C30-Pad2)") (class "Default")
      (node (ref "C30") (pin "2") (pinfunction "2_2") (pintype "passive"))
    )
    (net (code "52") (name "unconnected-(SIM1-VPP-Pad5)") (class "Default")
      (node (ref "SIM1") (pin "5") (pinfunction "VPP_5") (pintype "passive"))
    )
    (net (code "53") (name "unconnected-(U1A-PA0-WKUP1-Pad10)") (class "Default")
      (node (ref "U1") (pin "10") (pinfunction "PA0-WKUP1_10") (pintype "bidirectional"))
    )
    (net (code "54") (name "unconnected-(U1A-PA1-Pad11)") (class "Default")
      (node (ref "U1") (pin "11") (pinfunction "PA1_11") (pintype "bidirectional"))
    )
    (net (code "55") (name "unconnected-(U1A-PA6-Pad16)") (class "Default")
      (node (ref "U1") (pin "16") (pinfunction "PA6_16") (pintype "bidirectional"))
    )
    (net (code "56") (name "unconnected-(U1A-PA7-Pad17)") (class "Default")
      (node (ref "U1") (pin "17") (pinfunction "PA7_17") (pintype "bidirectional"))
    )
    (net (code "57") (name "unconnected-(U1A-PA8-Pad29)") (class "Default")
      (node (ref "U1") (pin "29") (pinfunction "PA8_29") (pintype "bidirectional"))
    )
    (net (code "58") (name "unconnected-(U1A-PA11-Pad32)") (class "Default")
      (node (ref "U1") (pin "32") (pinfunction "PA11_32") (pintype "bidirectional"))
    )
    (net (code "59") (name "unconnected-(U1A-PA12-Pad33)") (class "Default")
      (node (ref "U1") (pin "33") (pinfunction "PA12_33") (pintype "bidirectional"))
    )
    (net (code "60") (name "unconnected-(U1A-PA15-Pad38)") (class "Default")
      (node (ref "U1") (pin "38") (pinfunction "PA15_38") (pintype "bidirectional"))
    )
    (net (code "61") (name "unconnected-(U1A-PB0-Pad18)") (class "Default")
      (node (ref "U1") (pin "18") (pinfunction "PB0_18") (pintype "bidirectional"))
    )
    (net (code "62") (name "unconnected-(U1A-PB1-Pad19)") (class "Default")
      (node (ref "U1") (pin "19") (pinfunction "PB1_19") (pintype "bidirectional"))
    )
    (net (code "63") (name "unconnected-(U1A-PB2-Pad20)") (class "Default")
      (node (ref "U1") (pin "20") (pinfunction "PB2_20") (pintype "bidirectional"))
    )
    (net (code "64") (name "unconnected-(U1A-PB3-Pad39)") (class "Default")
      (node (ref "U1") (pin "39") (pinfunction "PB3_39") (pintype "bidirectional"))
    )
    (net (code "65") (name "unconnected-(U1A-PB4-Pad40)") (class "Default")
      (node (ref "U1") (pin "40") (pinfunction "PB4_40") (pintype "bidirectional"))
    )
    (net (code "66") (name "unconnected-(U1A-PB5-Pad41)") (class "Default")
      (node (ref "U1") (pin "41") (pinfunction "PB5_41") (pintype "bidirectional"))
    )
    (net (code "67") (name "unconnected-(U1A-PB6-Pad42)") (class "Default")
      (node (ref "U1") (pin "42") (pinfunction "PB6_42") (pintype "bidirectional"))
    )
    (net (code "68") (name "unconnected-(U1A-PB7-Pad43)") (class "Default")
      (node (ref "U1") (pin "43") (pinfunction "PB7_43") (pintype "bidirectional"))
    )
    (net (code "69") (name "unconnected-(U1A-PB8-Pad45)") (class "Default")
      (node (ref "U1") (pin "45") (pinfunction "PB8_45") (pintype "bidirectional"))
    )
    (net (code "70") (name "unconnected-(U1A-PB9-Pad46)") (class "Default")
      (node (ref "U1") (pin "46") (pinfunction "PB9_46") (pintype "bidirectional"))
    )
    (net (code "71") (name "unconnected-(U1A-PB13-Pad26)") (class "Default")
      (node (ref "U1") (pin "26") (pinfunction "PB13_26") (pintype "bidirectional"))
    )
    (net (code "72") (name "unconnected-(U1A-PB15-Pad28)") (class "Default")
      (node (ref "U1") (pin "28") (pinfunction "PB15_28") (pintype "bidirectional"))
    )
    (net (code "73") (name "unconnected-(U2A-ADC0-Pad9)") (class "Default")
      (node (ref "U2") (pin "9") (pinfunction "ADC0_9") (pintype "passive"))
    )
    (net (code "74") (name "unconnected-(U2A-NETLIGHT-Pad16)") (class "Default")
      (node (ref "U2") (pin "16") (pinfunction "NETLIGHT_16") (pintype "passive"))
    )
    (net (code "75") (name "unconnected-(U2A-PSM_EINT-Pad19)") (class "Default")
      (node (ref "U2") (pin "19") (pinfunction "PSM_EINT_19") (pintype "passive"))
    )
    (net (code "76") (name "unconnected-(U2A-RESERVED-Pad2)") (class "Default")
      (node (ref "U2") (pin "2") (pinfunction "RESERVED_2") (pintype "passive"))
    )
    (net (code "77") (name "unconnected-(U2A-RESERVED-Pad8)") (class "Default")
      (node (ref "U2") (pin "8") (pinfunction "RESERVED_8") (pintype "passive"))
    )
    (net (code "78") (name "unconnected-(U2A-RESERVED-Pad21)") (class "Default")
      (node (ref "U2") (pin "21") (pinfunction "RESERVED_21") (pintype "passive"))
    )
    (net (code "79") (name "unconnected-(U2A-RESERVED-Pad22)") (class "Default")
      (node (ref "U2") (pin "22") (pinfunction "RESERVED_22") (pintype "passive"))
    )
    (net (code "80") (name "unconnected-(U2A-RESERVED-Pad23)") (class "Default")
      (node (ref "U2") (pin "23") (pinfunction "RESERVED_23") (pintype "passive"))
    )
    (net (code "81") (name "unconnected-(U2A-RESERVED-Pad25)") (class "Default")
      (node (ref "U2") (pin "25") (pinfunction "RESERVED_25") (pintype "passive"))
    )
    (net (code "82") (name "unconnected-(U2A-RESERVED-Pad26)") (class "Default")
      (node (ref "U2") (pin "26") (pinfunction "RESERVED_26") (pintype "passive"))
    )
    (net (code "83") (name "unconnected-(U2A-RESERVED-Pad30)") (class "Default")
      (node (ref "U2") (pin "30") (pinfunction "RESERVED_30") (pintype "passive"))
    )
    (net (code "84") (name "unconnected-(U2A-RESERVED-Pad31)") (class "Default")
      (node (ref "U2") (pin "31") (pinfunction "RESERVED_31") (pintype "passive"))
    )
    (net (code "85") (name "unconnected-(U2A-RESERVED-Pad32)") (class "Default")
      (node (ref "U2") (pin "32") (pinfunction "RESERVED_32") (pintype "passive"))
    )
    (net (code "86") (name "unconnected-(U2A-RESERVED-Pad33)") (class "Default")
      (node (ref "U2") (pin "33") (pinfunction "RESERVED_33") (pintype "passive"))
    )
    (net (code "87") (name "unconnected-(U2A-RESERVED-Pad44)") (class "Default")
      (node (ref "U2") (pin "44") (pinfunction "RESERVED_44") (pintype "passive"))
    )
    (net (code "88") (name "unconnected-(U2A-RI-Pad20)") (class "Default")
      (node (ref "U2") (pin "20") (pinfunction "RI_20") (pintype "passive"))
    )
    (net (code "89") (name "unconnected-(U2A-RXD_AUX-Pad28)") (class "Default")
      (node (ref "U2") (pin "28") (pinfunction "RXD_AUX_28") (pintype "passive"))
    )
    (net (code "90") (name "unconnected-(U2A-SPI_CS-Pad6)") (class "Default")
      (node (ref "U2") (pin "6") (pinfunction "SPI_CS_6") (pintype "passive"))
    )
    (net (code "91") (name "unconnected-(U2A-SPI_MISO-Pad3)") (class "Default")
      (node (ref "U2") (pin "3") (pinfunction "SPI_MISO_3") (pintype "passive"))
    )
    (net (code "92") (name "unconnected-(U2A-SPI_MOSI-Pad4)") (class "Default")
      (node (ref "U2") (pin "4") (pinfunction "SPI_MOSI_4") (pintype "passive"))
    )
    (net (code "93") (name "unconnected-(U2A-SPI_SCLK-Pad5)") (class "Default")
      (node (ref "U2") (pin "5") (pinfunction "SPI_SCLK_5") (pintype "passive"))
    )
    (net (code "94") (name "unconnected-(U2A-TXD_AUX-Pad29)") (class "Default")
      (node (ref "U2") (pin "29") (pinfunction "TXD_AUX_29") (pintype "passive"))
    )
    (net (code "95") (name "unconnected-(U2B-RESERVED-Pad45)") (class "Default")
      (node (ref "U2") (pin "45") (pinfunction "RESERVED_45") (pintype "passive"))
    )
    (net (code "96") (name "unconnected-(U2B-RESERVED-Pad46)") (class "Default")
      (node (ref "U2") (pin "46") (pinfunction "RESERVED_46") (pintype "passive"))
    )
    (net (code "97") (name "unconnected-(U2B-RESERVED-Pad47)") (class "Default")
      (node (ref "U2") (pin "47") (pinfunction "RESERVED_47") (pintype "passive"))
    )
    (net (code "98") (name "unconnected-(U2B-RESERVED-Pad48)") (class "Default")
      (node (ref "U2") (pin "48") (pinfunction "RESERVED_48") (pintype "passive"))
    )
    (net (code "99") (name "unconnected-(U2B-RESERVED-Pad49)") (class "Default")
      (node (ref "U2") (pin "49") (pinfunction "RESERVED_49") (pintype "passive"))
    )
    (net (code "100") (name "unconnected-(U2B-RESERVED-Pad50)") (class "Default")
      (node (ref "U2") (pin "50") (pinfunction "RESERVED_50") (pintype "passive"))
    )
    (net (code "101") (name "unconnected-(U2B-RESERVED-Pad51)") (class "Default")
      (node (ref "U2") (pin "51") (pinfunction "RESERVED_51") (pintype "passive"))
    )
    (net (code "102") (name "unconnected-(U2B-RESERVED-Pad52)") (class "Default")
      (node (ref "U2") (pin "52") (pinfunction "RESERVED_52") (pintype "passive"))
    )
    (net (code "103") (name "unconnected-(U2B-RESERVED-Pad53)") (class "Default")
      (node (ref "U2") (pin "53") (pinfunction "RESERVED_53") (pintype "passive"))
    )
    (net (code "104") (name "unconnected-(U2B-RESERVED-Pad54)") (class "Default")
      (node (ref "U2") (pin "54") (pinfunction "RESERVED_54") (pintype "passive"))
    )
    (net (code "105") (name "unconnected-(U2B-RESERVED-Pad55)") (class "Default")
      (node (ref "U2") (pin "55") (pinfunction "RESERVED_55") (pintype "passive"))
    )
    (net (code "106") (name "unconnected-(U2B-RESERVED-Pad56)") (class "Default")
      (node (ref "U2") (pin "56") (pinfunction "RESERVED_56") (pintype "passive"))
    )
    (net (code "107") (name "unconnected-(U2B-RESERVED-Pad57)") (class "Default")
      (node (ref "U2") (pin "57") (pinfunction "RESERVED_57") (pintype "passive"))
    )
    (net (code "108") (name "unconnected-(U2B-RESERVED-Pad58)") (class "Default")
      (node (ref "U2") (pin "58") (pinfunction "RESERVED_58") (pintype "passive"))
    )
    (net (code "109") (name "unconnected-(U4-NC-Pad2)") (class "Default")
      (node (ref "U4") (pin "2") (pinfunction "NC_2") (pintype "passive"))
    )
    (net (code "110") (name "unconnected-(U4-NC-Pad4)") (class "Default")
      (node (ref "U4") (pin "4") (pinfunction "NC_4") (pintype "passive"))
    )
    (net (code "111") (name "unconnected-(U4-NC-Pad5)") (class "Default")
      (node (ref "U4") (pin "5") (pinfunction "NC_5") (pintype "passive"))
    )
  )
)
